# RADIO_nRF24L01.net
KiCad netlist of a schematic drawn in Altium Designer
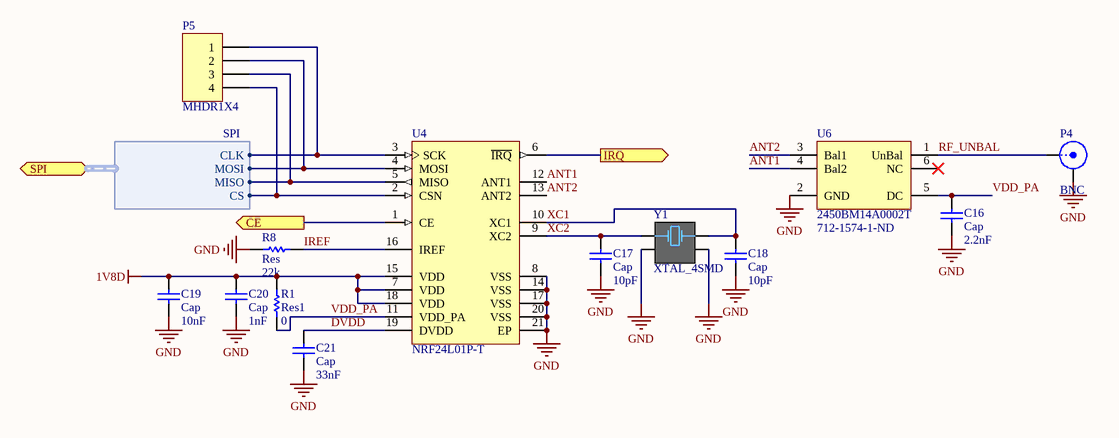
[diagram p0: RADIO_nRF24L01.SchDoc]

(export (version "E")
  (design (tool "Eeschema 10.0.6"))
  (components
    (comp (ref "C16")
      (value "Cap")
      (footprint "CAPC1005N")
      (description "Capacitor")
      (fields (field (name "ALTIUM_VALUE") "2.2nF") (field (name "PUBLISHER") "Altium Limited"))
      (libsource (lib "Miscellaneous Devices") (part "Cap"))
    )
    (comp (ref "C17")
      (value "Cap")
      (footprint "CAPC1005N")
      (description "Capacitor")
      (fields (field (name "ALTIUM_VALUE") "10pF") (field (name "PUBLISHER") "Altium Limited"))
      (libsource (lib "Miscellaneous Devices") (part "Cap"))
    )
    (comp (ref "C18")
      (value "Cap")
      (footprint "CAPC1005N")
      (description "Capacitor")
      (fields (field (name "ALTIUM_VALUE") "10pF") (field (name "PUBLISHER") "Altium Limited"))
      (libsource (lib "Miscellaneous Devices") (part "Cap"))
    )
    (comp (ref "C19")
      (value "Cap")
      (footprint "CAPC1005N")
      (description "Capacitor")
      (fields (field (name "ALTIUM_VALUE") "10nF") (field (name "PUBLISHER") "Altium Limited"))
      (libsource (lib "Miscellaneous Devices") (part "Cap"))
    )
    (comp (ref "C20")
      (value "Cap")
      (footprint "CAPC1005N")
      (description "Capacitor")
      (fields (field (name "ALTIUM_VALUE") "1nF") (field (name "PUBLISHER") "Altium Limited"))
      (libsource (lib "Miscellaneous Devices") (part "Cap"))
    )
    (comp (ref "C21")
      (value "Cap")
      (footprint "CAPC1005N")
      (description "Capacitor")
      (fields (field (name "ALTIUM_VALUE") "33nF") (field (name "PUBLISHER") "Altium Limited"))
      (libsource (lib "Miscellaneous Devices") (part "Cap"))
    )
    (comp (ref "P4")
      (value "BNC")
      (footprint "MCB3-V4")
      (description "BNC Elbow Connector")
      (fields (field (name "PUBLISHER") "Altium Limited"))
      (libsource (lib "Miscellaneous Connectors") (part "BNC"))
    )
    (comp (ref "P5")
      (value "MHDR1X4")
      (footprint "MHDR1X4")
      (description "Header, 4-Pin")
      (fields (field (name "PUBLISHER") "Altium Limited"))
      (libsource (lib "Miscellaneous Connectors") (part "MHDR1X4"))
    )
    (comp (ref "R1")
      (value "Res1")
      (footprint "RESC1005N")
      (description "Resistor")
      (fields (field (name "ALTIUM_VALUE") "0") (field (name "PUBLISHER") "Altium Limited"))
      (libsource (lib "Miscellaneous Devices") (part "Res1"))
    )
    (comp (ref "R8")
      (value "Res")
      (footprint "RESC1005N")
      (description "Resistor")
      (fields (field (name "ALTIUM_VALUE") "22k") (field (name "PUBLISHER") "Altium Limited"))
      (libsource (lib "Miscellaneous Devices") (part "Res1"))
    )
    (comp (ref "U4")
      (value "NRF24L01P-T")
      (footprint "NRSC-QFN-20_L")
      (description "Single Chip Transceiver, 2.4 GHz, 60 mW, 1.9 to 3.6 V, -40 to 85 degC, 20-Pin QFN, RoHS, Tray")
      (fields (field (name "MANUFACTURER") "Nordic Semiconductor"))
      (libsource (lib "Components - 28.10.19 - 20.35") (part "CMP-2000-06859-1"))
    )
    (comp (ref "U6")
      (value "2450BM14A0002T")
      (footprint "2450BM14A0002")
      (description "JOHANSON TECHNOLOGY - 2450BM14A0002T - BALUN, 2.45GHZ, IMPEDANCE MATCHED")
      (fields (field (name "SUPPLIER PART NUMBER 1") "712-1574-1-ND"))
      (libsource (lib "Schlib1") (part "2450BM14A0002T"))
    )
    (comp (ref "Y1")
      (value "XTAL_4SMD")
      (footprint "XTAL3225-4-N")
      (description "Crystal Oscillator (4 pin)")
      (fields (field (name "PUBLISHER") "Altium Limited"))
      (libsource (lib "Miscellaneous Devices") (part "XTAL_4SMD"))
    )
  )
  (nets
    (net (code "2") (name "/ANT1") (class "Default")
      (node (ref "U4") (pin "12") (pinfunction "ANT1_12") (pintype "passive"))
      (node (ref "U6") (pin "4") (pinfunction "Bal2_4") (pintype "passive"))
    )
    (net (code "3") (name "/ANT2") (class "Default")
      (node (ref "U4") (pin "13") (pinfunction "ANT2_13") (pintype "passive"))
      (node (ref "U6") (pin "3") (pinfunction "Bal1_3") (pintype "passive"))
    )
    (net (code "4") (name "/CE") (class "Default")
      (node (ref "U4") (pin "1") (pinfunction "CE_1") (pintype "input"))
    )
    (net (code "5") (name "/DVDD") (class "Default")
      (node (ref "C21") (pin "2") (pinfunction "2_2") (pintype "passive"))
      (node (ref "U4") (pin "19") (pinfunction "DVDD_19") (pintype "power_in"))
    )
    (net (code "6") (name "/IREF") (class "Default")
      (node (ref "R8") (pin "2") (pinfunction "2_2") (pintype "passive"))
      (node (ref "U4") (pin "16") (pinfunction "IREF_16") (pintype "passive"))
    )
    (net (code "7") (name "/IRQ") (class "Default")
      (node (ref "U4") (pin "6") (pinfunction "~{IRQ}_6") (pintype "output"))
    )
    (net (code "8") (name "/RF_UNBAL") (class "Default")
      (node (ref "P4") (pin "1") (pinfunction "X_1") (pintype "passive"))
      (node (ref "U6") (pin "1") (pinfunction "UnBal_1") (pintype "passive"))
    )
    (net (code "9") (name "/VDD_PA") (class "Default")
      (node (ref "C16") (pin "2") (pinfunction "2_2") (pintype "passive"))
      (node (ref "R1") (pin "1") (pinfunction "1_1") (pintype "passive"))
      (node (ref "U4") (pin "11") (pinfunction "VDD_PA_11") (pintype "power_in"))
      (node (ref "U6") (pin "5") (pinfunction "DC_5") (pintype "passive"))
    )
    (net (code "10") (name "/XC1") (class "Default")
      (node (ref "C18") (pin "2") (pinfunction "2_2") (pintype "passive"))
      (node (ref "U4") (pin "10") (pinfunction "XC1_10") (pintype "passive"))
      (node (ref "Y1") (pin "3") (pinfunction "OSC2_3") (pintype "passive"))
    )
    (net (code "11") (name "/XC2") (class "Default")
      (node (ref "C17") (pin "2") (pinfunction "2_2") (pintype "passive"))
      (node (ref "U4") (pin "9") (pinfunction "XC2_9") (pintype "passive"))
      (node (ref "Y1") (pin "1") (pinfunction "OSC1_1") (pintype "passive"))
    )
    (net (code "13") (name "1V8D") (class "Default")
      (node (ref "C19") (pin "2") (pinfunction "2_2") (pintype "passive"))
      (node (ref "C20") (pin "2") (pinfunction "2_2") (pintype "passive"))
      (node (ref "R1") (pin "2") (pinfunction "2_2") (pintype "passive"))
      (node (ref "U4") (pin "15") (pinfunction "VDD_15") (pintype "power_in"))
      (node (ref "U4") (pin "18") (pinfunction "VDD_18") (pintype "power_in"))
      (node (ref "U4") (pin "7") (pinfunction "VDD_7") (pintype "power_in"))
    )
    (net (code "14") (name "GND") (class "Default")
      (node (ref "C16") (pin "1") (pinfunction "1_1") (pintype "passive"))
      (node (ref "C17") (pin "1") (pinfunction "1_1") (pintype "passive"))
      (node (ref "C18") (pin "1") (pinfunction "1_1") (pintype "passive"))
      (node (ref "C19") (pin "1") (pinfunction "1_1") (pintype "passive"))
      (node (ref "C20") (pin "1") (pinfunction "1_1") (pintype "passive"))
      (node (ref "C21") (pin "1") (pinfunction "1_1") (pintype "passive"))
      (node (ref "P4") (pin "2") (pinfunction "Y_2") (pintype "passive"))
      (node (ref "R8") (pin "1") (pinfunction "1_1") (pintype "passive"))
      (node (ref "U4") (pin "14") (pinfunction "VSS_14") (pintype "power_in"))
      (node (ref "U4") (pin "17") (pinfunction "VSS_17") (pintype "power_in"))
      (node (ref "U4") (pin "20") (pinfunction "VSS_20") (pintype "power_in"))
      (node (ref "U4") (pin "21") (pinfunction "EP_21") (pintype "passive"))
      (node (ref "U4") (pin "8") (pinfunction "VSS_8") (pintype "power_in"))
      (node (ref "U6") (pin "2") (pinfunction "GND_2") (pintype "passive"))
      (node (ref "Y1") (pin "2") (pinfunction "2_2") (pintype "power_in"))
      (node (ref "Y1") (pin "4") (pinfunction "4_4") (pintype "power_in"))
    )
    (net (code "15") (name "Net-(U4-CSN)") (class "Default")
      (node (ref "P5") (pin "4") (pinfunction "4_4") (pintype "passive"))
      (node (ref "U4") (pin "2") (pinfunction "CSN_2") (pintype "input"))
    )
    (net (code "16") (name "Net-(U4-MISO)") (class "Default")
      (node (ref "P5") (pin "3") (pinfunction "3_3") (pintype "passive"))
      (node (ref "U4") (pin "5") (pinfunction "MISO_5") (pintype "output"))
    )
    (net (code "17") (name "Net-(U4-MOSI)") (class "Default")
      (node (ref "P5") (pin "2") (pinfunction "2_2") (pintype "passive"))
      (node (ref "U4") (pin "4") (pinfunction "MOSI_4") (pintype "input"))
    )
    (net (code "18") (name "Net-(U4-SCK)") (class "Default")
      (node (ref "P5") (pin "1") (pinfunction "1_1") (pintype "passive"))
      (node (ref "U4") (pin "3") (pinfunction "SCK_3") (pintype "input"))
    )
    (net (code "19") (name "unconnected-(U6-NC-Pad6)") (class "Default")
      (node (ref "U6") (pin "6") (pinfunction "NC_6") (pintype "passive+no_connect"))
    )
  )
)
